# connectors.net
KiCad netlist of a schematic drawn in Altium Designer
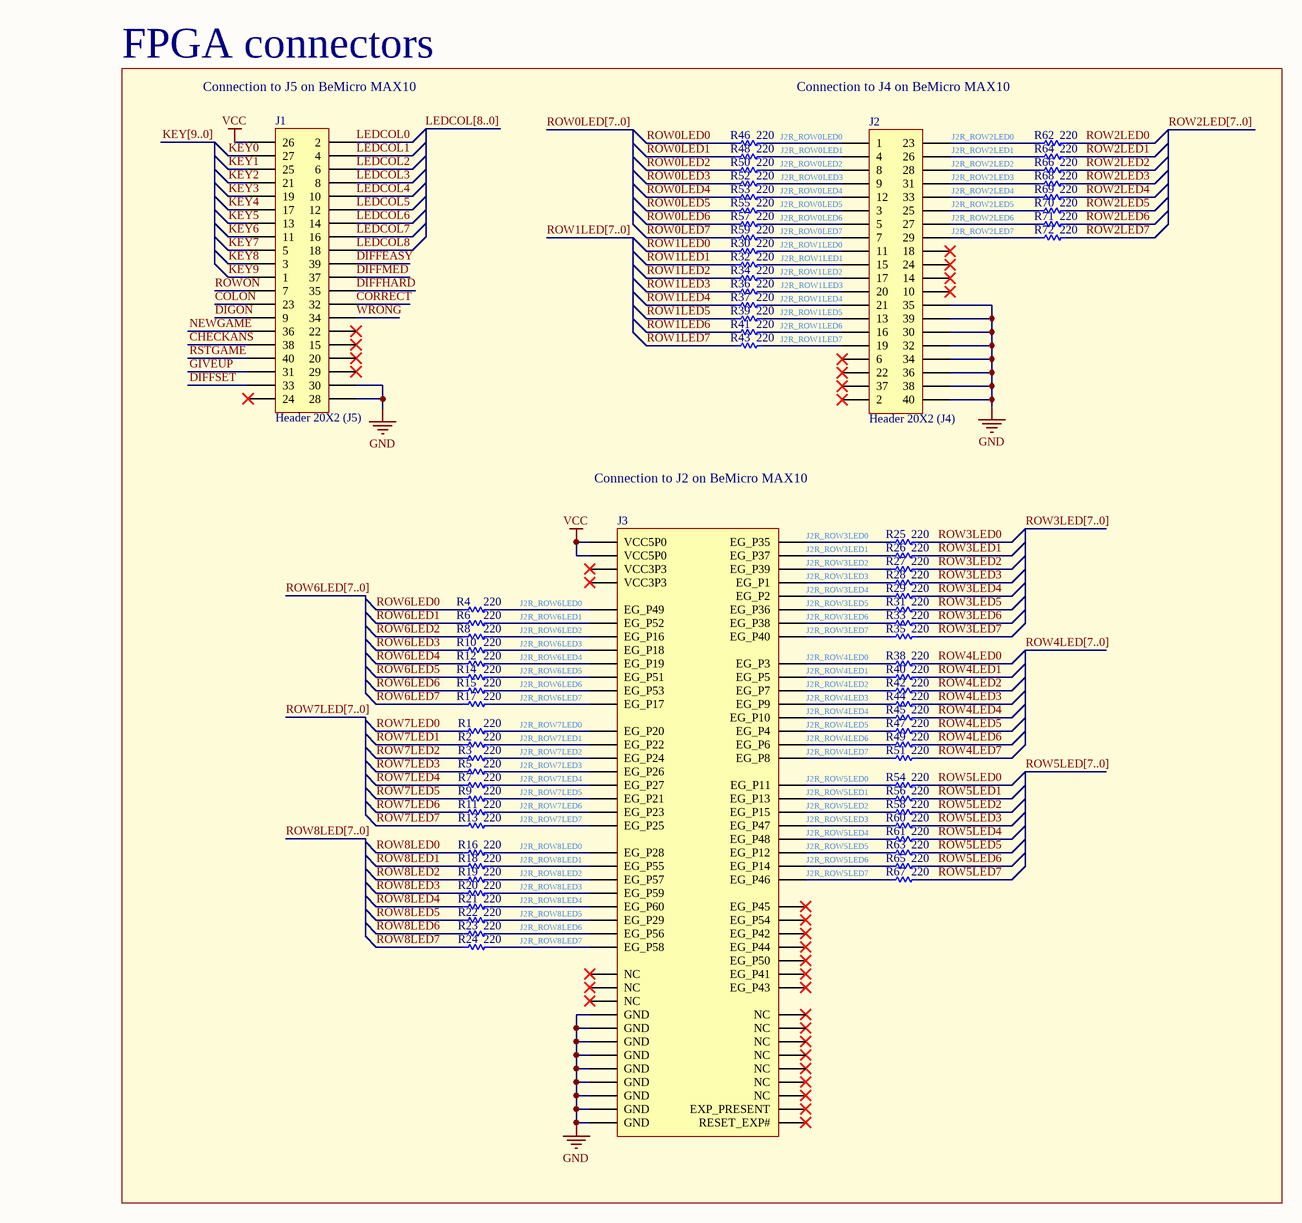
[diagram p0: connectors.SchDoc]

(export (version "E")
  (design (tool "Eeschema 10.0.6"))
  (components
    (comp (ref "J1")
      (value "Header 20X2 (J5)")
      (footprint "2x20")
      (description "Header, 20-Pin, Dual row")
      (fields (field (name "PUBLISHER") "Altium Limited"))
      (libsource (lib "") (part "Header 20X2_1"))
    )
    (comp (ref "J2")
      (value "Header 20X2 (J4)")
      (footprint "2x20")
      (description "Header, 20-Pin, Dual row")
      (fields (field (name "PUBLISHER") "Altium Limited"))
      (libsource (lib "bemicro_max10_fpga_connectors") (part "Header 20X2"))
    )
    (comp (ref "J3")
      (value "~")
      (footprint "SAMTEC_MEC6-140-02-L-D-RA1-TR")
      (description "Edge connector")
      (fields (field (name "MF") "Samtec") (field (name "MP") "MEC6-140-02-L-D-RA1-TR"))
      (libsource (lib "bemicro_max10_fpga_connectors") (part "MEC6-140-02-L-D-RA1-TR"))
    )
    (comp (ref "R1")
      (value "220")
      (footprint "SMD-0805-RES")
      (description "Resistor")
      (fields (field (name "Comment") "Res1") (field (name "PUBLISHER") "Altium Limited"))
      (libsource (lib "Miscellaneous Devices") (part "Res1"))
    )
    (comp (ref "R2")
      (value "220")
      (footprint "SMD-0805-RES")
      (description "Resistor")
      (fields (field (name "Comment") "Res1") (field (name "PUBLISHER") "Altium Limited"))
      (libsource (lib "Miscellaneous Devices") (part "Res1"))
    )
    (comp (ref "R3")
      (value "220")
      (footprint "SMD-0805-RES")
      (description "Resistor")
      (fields (field (name "Comment") "Res1") (field (name "PUBLISHER") "Altium Limited"))
      (libsource (lib "Miscellaneous Devices") (part "Res1"))
    )
    (comp (ref "R4")
      (value "220")
      (footprint "SMD-0805-RES")
      (description "Resistor")
      (fields (field (name "Comment") "Res1") (field (name "PUBLISHER") "Altium Limited"))
      (libsource (lib "Miscellaneous Devices") (part "Res1"))
    )
    (comp (ref "R5")
      (value "220")
      (footprint "SMD-0805-RES")
      (description "Resistor")
      (fields (field (name "Comment") "Res1") (field (name "PUBLISHER") "Altium Limited"))
      (libsource (lib "Miscellaneous Devices") (part "Res1"))
    )
    (comp (ref "R6")
      (value "220")
      (footprint "SMD-0805-RES")
      (description "Resistor")
      (fields (field (name "Comment") "Res1") (field (name "PUBLISHER") "Altium Limited"))
      (libsource (lib "Miscellaneous Devices") (part "Res1"))
    )
    (comp (ref "R7")
      (value "220")
      (footprint "SMD-0805-RES")
      (description "Resistor")
      (fields (field (name "Comment") "Res1") (field (name "PUBLISHER") "Altium Limited"))
      (libsource (lib "Miscellaneous Devices") (part "Res1"))
    )
    (comp (ref "R8")
      (value "220")
      (footprint "SMD-0805-RES")
      (description "Resistor")
      (fields (field (name "Comment") "Res1") (field (name "PUBLISHER") "Altium Limited"))
      (libsource (lib "Miscellaneous Devices") (part "Res1"))
    )
    (comp (ref "R9")
      (value "220")
      (footprint "SMD-0805-RES")
      (description "Resistor")
      (fields (field (name "Comment") "Res1") (field (name "PUBLISHER") "Altium Limited"))
      (libsource (lib "Miscellaneous Devices") (part "Res1"))
    )
    (comp (ref "R10")
      (value "220")
      (footprint "SMD-0805-RES")
      (description "Resistor")
      (fields (field (name "Comment") "Res1") (field (name "PUBLISHER") "Altium Limited"))
      (libsource (lib "Miscellaneous Devices") (part "Res1"))
    )
    (comp (ref "R11")
      (value "220")
      (footprint "SMD-0805-RES")
      (description "Resistor")
      (fields (field (name "Comment") "Res1") (field (name "PUBLISHER") "Altium Limited"))
      (libsource (lib "Miscellaneous Devices") (part "Res1"))
    )
    (comp (ref "R12")
      (value "220")
      (footprint "SMD-0805-RES")
      (description "Resistor")
      (fields (field (name "Comment") "Res1") (field (name "PUBLISHER") "Altium Limited"))
      (libsource (lib "Miscellaneous Devices") (part "Res1"))
    )
    (comp (ref "R13")
      (value "220")
      (footprint "SMD-0805-RES")
      (description "Resistor")
      (fields (field (name "Comment") "Res1") (field (name "PUBLISHER") "Altium Limited"))
      (libsource (lib "Miscellaneous Devices") (part "Res1"))
    )
    (comp (ref "R14")
      (value "220")
      (footprint "SMD-0805-RES")
      (description "Resistor")
      (fields (field (name "Comment") "Res1") (field (name "PUBLISHER") "Altium Limited"))
      (libsource (lib "Miscellaneous Devices") (part "Res1"))
    )
    (comp (ref "R15")
      (value "220")
      (footprint "SMD-0805-RES")
      (description "Resistor")
      (fields (field (name "Comment") "Res1") (field (name "PUBLISHER") "Altium Limited"))
      (libsource (lib "Miscellaneous Devices") (part "Res1"))
    )
    (comp (ref "R16")
      (value "220")
      (footprint "SMD-0805-RES")
      (description "Resistor")
      (fields (field (name "Comment") "Res1") (field (name "PUBLISHER") "Altium Limited"))
      (libsource (lib "Miscellaneous Devices") (part "Res1"))
    )
    (comp (ref "R17")
      (value "220")
      (footprint "SMD-0805-RES")
      (description "Resistor")
      (fields (field (name "Comment") "Res1") (field (name "PUBLISHER") "Altium Limited"))
      (libsource (lib "Miscellaneous Devices") (part "Res1"))
    )
    (comp (ref "R18")
      (value "220")
      (footprint "SMD-0805-RES")
      (description "Resistor")
      (fields (field (name "Comment") "Res1") (field (name "PUBLISHER") "Altium Limited"))
      (libsource (lib "Miscellaneous Devices") (part "Res1"))
    )
    (comp (ref "R19")
      (value "220")
      (footprint "SMD-0805-RES")
      (description "Resistor")
      (fields (field (name "Comment") "Res1") (field (name "PUBLISHER") "Altium Limited"))
      (libsource (lib "Miscellaneous Devices") (part "Res1"))
    )
    (comp (ref "R20")
      (value "220")
      (footprint "SMD-0805-RES")
      (description "Resistor")
      (fields (field (name "Comment") "Res1") (field (name "PUBLISHER") "Altium Limited"))
      (libsource (lib "Miscellaneous Devices") (part "Res1"))
    )
    (comp (ref "R21")
      (value "220")
      (footprint "SMD-0805-RES")
      (description "Resistor")
      (fields (field (name "Comment") "Res1") (field (name "PUBLISHER") "Altium Limited"))
      (libsource (lib "Miscellaneous Devices") (part "Res1"))
    )
    (comp (ref "R22")
      (value "220")
      (footprint "SMD-0805-RES")
      (description "Resistor")
      (fields (field (name "Comment") "Res1") (field (name "PUBLISHER") "Altium Limited"))
      (libsource (lib "Miscellaneous Devices") (part "Res1"))
    )
    (comp (ref "R23")
      (value "220")
      (footprint "SMD-0805-RES")
      (description "Resistor")
      (fields (field (name "Comment") "Res1") (field (name "PUBLISHER") "Altium Limited"))
      (libsource (lib "Miscellaneous Devices") (part "Res1"))
    )
    (comp (ref "R24")
      (value "220")
      (footprint "SMD-0805-RES")
      (description "Resistor")
      (fields (field (name "Comment") "Res1") (field (name "PUBLISHER") "Altium Limited"))
      (libsource (lib "Miscellaneous Devices") (part "Res1"))
    )
    (comp (ref "R25")
      (value "220")
      (footprint "SMD-0805-RES")
      (description "Resistor")
      (fields (field (name "Comment") "Res1") (field (name "PUBLISHER") "Altium Limited"))
      (libsource (lib "Miscellaneous Devices") (part "Res1"))
    )
    (comp (ref "R26")
      (value "220")
      (footprint "SMD-0805-RES")
      (description "Resistor")
      (fields (field (name "Comment") "Res1") (field (name "PUBLISHER") "Altium Limited"))
      (libsource (lib "Miscellaneous Devices") (part "Res1"))
    )
    (comp (ref "R27")
      (value "220")
      (footprint "SMD-0805-RES")
      (description "Resistor")
      (fields (field (name "Comment") "Res1") (field (name "PUBLISHER") "Altium Limited"))
      (libsource (lib "Miscellaneous Devices") (part "Res1"))
    )
    (comp (ref "R28")
      (value "220")
      (footprint "SMD-0805-RES")
      (description "Resistor")
      (fields (field (name "Comment") "Res1") (field (name "PUBLISHER") "Altium Limited"))
      (libsource (lib "Miscellaneous Devices") (part "Res1"))
    )
    (comp (ref "R29")
      (value "220")
      (footprint "SMD-0805-RES")
      (description "Resistor")
      (fields (field (name "Comment") "Res1") (field (name "PUBLISHER") "Altium Limited"))
      (libsource (lib "Miscellaneous Devices") (part "Res1"))
    )
    (comp (ref "R30")
      (value "220")
      (footprint "SMD-0805-RES")
      (description "Resistor")
      (fields (field (name "Comment") "Res1") (field (name "PUBLISHER") "Altium Limited"))
      (libsource (lib "Miscellaneous Devices") (part "Res1"))
    )
    (comp (ref "R31")
      (value "220")
      (footprint "SMD-0805-RES")
      (description "Resistor")
      (fields (field (name "Comment") "Res1") (field (name "PUBLISHER") "Altium Limited"))
      (libsource (lib "Miscellaneous Devices") (part "Res1"))
    )
    (comp (ref "R32")
      (value "220")
      (footprint "SMD-0805-RES")
      (description "Resistor")
      (fields (field (name "Comment") "Res1") (field (name "PUBLISHER") "Altium Limited"))
      (libsource (lib "Miscellaneous Devices") (part "Res1"))
    )
    (comp (ref "R33")
      (value "220")
      (footprint "SMD-0805-RES")
      (description "Resistor")
      (fields (field (name "Comment") "Res1") (field (name "PUBLISHER") "Altium Limited"))
      (libsource (lib "Miscellaneous Devices") (part "Res1"))
    )
    (comp (ref "R34")
      (value "220")
      (footprint "SMD-0805-RES")
      (description "Resistor")
      (fields (field (name "Comment") "Res1") (field (name "PUBLISHER") "Altium Limited"))
      (libsource (lib "Miscellaneous Devices") (part "Res1"))
    )
    (comp (ref "R35")
      (value "220")
      (footprint "SMD-0805-RES")
      (description "Resistor")
      (fields (field (name "Comment") "Res1") (field (name "PUBLISHER") "Altium Limited"))
      (libsource (lib "Miscellaneous Devices") (part "Res1"))
    )
    (comp (ref "R36")
      (value "220")
      (footprint "SMD-0805-RES")
      (description "Resistor")
      (fields (field (name "Comment") "Res1") (field (name "PUBLISHER") "Altium Limited"))
      (libsource (lib "Miscellaneous Devices") (part "Res1"))
    )
    (comp (ref "R37")
      (value "220")
      (footprint "SMD-0805-RES")
      (description "Resistor")
      (fields (field (name "Comment") "Res1") (field (name "PUBLISHER") "Altium Limited"))
      (libsource (lib "Miscellaneous Devices") (part "Res1"))
    )
    (comp (ref "R38")
      (value "220")
      (footprint "SMD-0805-RES")
      (description "Resistor")
      (fields (field (name "Comment") "Res1") (field (name "PUBLISHER") "Altium Limited"))
      (libsource (lib "Miscellaneous Devices") (part "Res1"))
    )
    (comp (ref "R39")
      (value "220")
      (footprint "SMD-0805-RES")
      (description "Resistor")
      (fields (field (name "Comment") "Res1") (field (name "PUBLISHER") "Altium Limited"))
      (libsource (lib "Miscellaneous Devices") (part "Res1"))
    )
    (comp (ref "R40")
      (value "220")
      (footprint "SMD-0805-RES")
      (description "Resistor")
      (fields (field (name "Comment") "Res1") (field (name "PUBLISHER") "Altium Limited"))
      (libsource (lib "Miscellaneous Devices") (part "Res1"))
    )
    (comp (ref "R41")
      (value "220")
      (footprint "SMD-0805-RES")
      (description "Resistor")
      (fields (field (name "Comment") "Res1") (field (name "PUBLISHER") "Altium Limited"))
      (libsource (lib "Miscellaneous Devices") (part "Res1"))
    )
    (comp (ref "R42")
      (value "220")
      (footprint "SMD-0805-RES")
      (description "Resistor")
      (fields (field (name "Comment") "Res1") (field (name "PUBLISHER") "Altium Limited"))
      (libsource (lib "Miscellaneous Devices") (part "Res1"))
    )
    (comp (ref "R43")
      (value "220")
      (footprint "SMD-0805-RES")
      (description "Resistor")
      (fields (field (name "Comment") "Res1") (field (name "PUBLISHER") "Altium Limited"))
      (libsource (lib "Miscellaneous Devices") (part "Res1"))
    )
    (comp (ref "R44")
      (value "220")
      (footprint "SMD-0805-RES")
      (description "Resistor")
      (fields (field (name "Comment") "Res1") (field (name "PUBLISHER") "Altium Limited"))
      (libsource (lib "Miscellaneous Devices") (part "Res1"))
    )
    (comp (ref "R45")
      (value "220")
      (footprint "SMD-0805-RES")
      (description "Resistor")
      (fields (field (name "Comment") "Res1") (field (name "PUBLISHER") "Altium Limited"))
      (libsource (lib "Miscellaneous Devices") (part "Res1"))
    )
    (comp (ref "R46")
      (value "220")
      (footprint "SMD-0805-RES")
      (description "Resistor")
      (fields (field (name "Comment") "Res1") (field (name "PUBLISHER") "Altium Limited"))
      (libsource (lib "Miscellaneous Devices") (part "Res1"))
    )
    (comp (ref "R47")
      (value "220")
      (footprint "SMD-0805-RES")
      (description "Resistor")
      (fields (field (name "Comment") "Res1") (field (name "PUBLISHER") "Altium Limited"))
      (libsource (lib "Miscellaneous Devices") (part "Res1"))
    )
    (comp (ref "R48")
      (value "220")
      (footprint "SMD-0805-RES")
      (description "Resistor")
      (fields (field (name "Comment") "Res1") (field (name "PUBLISHER") "Altium Limited"))
      (libsource (lib "Miscellaneous Devices") (part "Res1"))
    )
    (comp (ref "R49")
      (value "220")
      (footprint "SMD-0805-RES")
      (description "Resistor")
      (fields (field (name "Comment") "Res1") (field (name "PUBLISHER") "Altium Limited"))
      (libsource (lib "Miscellaneous Devices") (part "Res1"))
    )
    (comp (ref "R50")
      (value "220")
      (footprint "SMD-0805-RES")
      (description "Resistor")
      (fields (field (name "Comment") "Res1") (field (name "PUBLISHER") "Altium Limited"))
      (libsource (lib "Miscellaneous Devices") (part "Res1"))
    )
    (comp (ref "R51")
      (value "220")
      (footprint "SMD-0805-RES")
      (description "Resistor")
      (fields (field (name "Comment") "Res1") (field (name "PUBLISHER") "Altium Limited"))
      (libsource (lib "Miscellaneous Devices") (part "Res1"))
    )
    (comp (ref "R52")
      (value "220")
      (footprint "SMD-0805-RES")
      (description "Resistor")
      (fields (field (name "Comment") "Res1") (field (name "PUBLISHER") "Altium Limited"))
      (libsource (lib "Miscellaneous Devices") (part "Res1"))
    )
    (comp (ref "R53")
      (value "220")
      (footprint "SMD-0805-RES")
      (description "Resistor")
      (fields (field (name "Comment") "Res1") (field (name "PUBLISHER") "Altium Limited"))
      (libsource (lib "Miscellaneous Devices") (part "Res1"))
    )
    (comp (ref "R54")
      (value "220")
      (footprint "SMD-0805-RES")
      (description "Resistor")
      (fields (field (name "Comment") "Res1") (field (name "PUBLISHER") "Altium Limited"))
      (libsource (lib "Miscellaneous Devices") (part "Res1"))
    )
    (comp (ref "R55")
      (value "220")
      (footprint "SMD-0805-RES")
      (description "Resistor")
      (fields (field (name "Comment") "Res1") (field (name "PUBLISHER") "Altium Limited"))
      (libsource (lib "Miscellaneous Devices") (part "Res1"))
    )
    (comp (ref "R56")
      (value "220")
      (footprint "SMD-0805-RES")
      (description "Resistor")
      (fields (field (name "Comment") "Res1") (field (name "PUBLISHER") "Altium Limited"))
      (libsource (lib "Miscellaneous Devices") (part "Res1"))
    )
    (comp (ref "R57")
      (value "220")
      (footprint "SMD-0805-RES")
      (description "Resistor")
      (fields (field (name "Comment") "Res1") (field (name "PUBLISHER") "Altium Limited"))
      (libsource (lib "Miscellaneous Devices") (part "Res1"))
    )
    (comp (ref "R58")
      (value "220")
      (footprint "SMD-0805-RES")
      (description "Resistor")
      (fields (field (name "Comment") "Res1") (field (name "PUBLISHER") "Altium Limited"))
      (libsource (lib "Miscellaneous Devices") (part "Res1"))
    )
    (comp (ref "R59")
      (value "220")
      (footprint "SMD-0805-RES")
      (description "Resistor")
      (fields (field (name "Comment") "Res1") (field (name "PUBLISHER") "Altium Limited"))
      (libsource (lib "Miscellaneous Devices") (part "Res1"))
    )
    (comp (ref "R60")
      (value "220")
      (footprint "SMD-0805-RES")
      (description "Resistor")
      (fields (field (name "Comment") "Res1") (field (name "PUBLISHER") "Altium Limited"))
      (libsource (lib "Miscellaneous Devices") (part "Res1"))
    )
    (comp (ref "R61")
      (value "220")
      (footprint "SMD-0805-RES")
      (description "Resistor")
      (fields (field (name "Comment") "Res1") (field (name "PUBLISHER") "Altium Limited"))
      (libsource (lib "Miscellaneous Devices") (part "Res1"))
    )
    (comp (ref "R62")
      (value "220")
      (footprint "SMD-0805-RES")
      (description "Resistor")
      (fields (field (name "Comment") "Res1") (field (name "PUBLISHER") "Altium Limited"))
      (libsource (lib "Miscellaneous Devices") (part "Res1"))
    )
    (comp (ref "R63")
      (value "220")
      (footprint "SMD-0805-RES")
      (description "Resistor")
      (fields (field (name "Comment") "Res1") (field (name "PUBLISHER") "Altium Limited"))
      (libsource (lib "Miscellaneous Devices") (part "Res1"))
    )
    (comp (ref "R64")
      (value "220")
      (footprint "SMD-0805-RES")
      (description "Resistor")
      (fields (field (name "Comment") "Res1") (field (name "PUBLISHER") "Altium Limited"))
      (libsource (lib "Miscellaneous Devices") (part "Res1"))
    )
    (comp (ref "R65")
      (value "220")
      (footprint "SMD-0805-RES")
      (description "Resistor")
      (fields (field (name "Comment") "Res1") (field (name "PUBLISHER") "Altium Limited"))
      (libsource (lib "Miscellaneous Devices") (part "Res1"))
    )
    (comp (ref "R66")
      (value "220")
      (footprint "SMD-0805-RES")
      (description "Resistor")
      (fields (field (name "Comment") "Res1") (field (name "PUBLISHER") "Altium Limited"))
      (libsource (lib "Miscellaneous Devices") (part "Res1"))
    )
    (comp (ref "R67")
      (value "220")
      (footprint "SMD-0805-RES")
      (description "Resistor")
      (fields (field (name "Comment") "Res1") (field (name "PUBLISHER") "Altium Limited"))
      (libsource (lib "Miscellaneous Devices") (part "Res1"))
    )
    (comp (ref "R68")
      (value "220")
      (footprint "SMD-0805-RES")
      (description "Resistor")
      (fields (field (name "Comment") "Res1") (field (name "PUBLISHER") "Altium Limited"))
      (libsource (lib "Miscellaneous Devices") (part "Res1"))
    )
    (comp (ref "R69")
      (value "220")
      (footprint "SMD-0805-RES")
      (description "Resistor")
      (fields (field (name "Comment") "Res1") (field (name "PUBLISHER") "Altium Limited"))
      (libsource (lib "Miscellaneous Devices") (part "Res1"))
    )
    (comp (ref "R70")
      (value "220")
      (footprint "SMD-0805-RES")
      (description "Resistor")
      (fields (field (name "Comment") "Res1") (field (name "PUBLISHER") "Altium Limited"))
      (libsource (lib "Miscellaneous Devices") (part "Res1"))
    )
    (comp (ref "R71")
      (value "220")
      (footprint "SMD-0805-RES")
      (description "Resistor")
      (fields (field (name "Comment") "Res1") (field (name "PUBLISHER") "Altium Limited"))
      (libsource (lib "Miscellaneous Devices") (part "Res1"))
    )
    (comp (ref "R72")
      (value "220")
      (footprint "SMD-0805-RES")
      (description "Resistor")
      (fields (field (name "Comment") "Res1") (field (name "PUBLISHER") "Altium Limited"))
      (libsource (lib "Miscellaneous Devices") (part "Res1"))
    )
  )
  (nets
    (net (code "1") (name "/CHECKANS") (class "Default")
      (node (ref "J1") (pin "38") (pinfunction "38_38") (pintype "passive"))
    )
    (net (code "2") (name "/COLON") (class "Default")
      (node (ref "J1") (pin "23") (pinfunction "23_23") (pintype "passive"))
    )
    (net (code "3") (name "/CORRECT") (class "Default")
      (node (ref "J1") (pin "32") (pinfunction "32_32") (pintype "passive"))
    )
    (net (code "4") (name "/DIFFEASY") (class "Default")
      (node (ref "J1") (pin "39") (pinfunction "39_39") (pintype "passive"))
    )
    (net (code "5") (name "/DIFFHARD") (class "Default")
      (node (ref "J1") (pin "35") (pinfunction "35_35") (pintype "passive"))
    )
    (net (code "6") (name "/DIFFMED") (class "Default")
      (node (ref "J1") (pin "37") (pinfunction "37_37") (pintype "passive"))
    )
    (net (code "7") (name "/DIFFSET") (class "Default")
      (node (ref "J1") (pin "33") (pinfunction "33_33") (pintype "passive"))
    )
    (net (code "8") (name "/DIGON") (class "Default")
      (node (ref "J1") (pin "9") (pinfunction "9_9") (pintype "passive"))
    )
    (net (code "9") (name "/GIVEUP") (class "Default")
      (node (ref "J1") (pin "31") (pinfunction "31_31") (pintype "passive"))
    )
    (net (code "10") (name "/J2R_ROW0LED0") (class "Default")
      (node (ref "J2") (pin "1") (pinfunction "1_1") (pintype "passive"))
      (node (ref "R46") (pin "2") (pinfunction "2_2") (pintype "passive"))
    )
    (net (code "11") (name "/J2R_ROW0LED1") (class "Default")
      (node (ref "J2") (pin "4") (pinfunction "4_4") (pintype "passive"))
      (node (ref "R48") (pin "2") (pinfunction "2_2") (pintype "passive"))
    )
    (net (code "12") (name "/J2R_ROW0LED2") (class "Default")
      (node (ref "J2") (pin "8") (pinfunction "8_8") (pintype "passive"))
      (node (ref "R50") (pin "2") (pinfunction "2_2") (pintype "passive"))
    )
    (net (code "13") (name "/J2R_ROW0LED3") (class "Default")
      (node (ref "J2") (pin "9") (pinfunction "9_9") (pintype "passive"))
      (node (ref "R52") (pin "2") (pinfunction "2_2") (pintype "passive"))
    )
    (net (code "14") (name "/J2R_ROW0LED4") (class "Default")
      (node (ref "J2") (pin "12") (pinfunction "12_12") (pintype "passive"))
      (node (ref "R53") (pin "2") (pinfunction "2_2") (pintype "passive"))
    )
    (net (code "15") (name "/J2R_ROW0LED5") (class "Default")
      (node (ref "J2") (pin "3") (pinfunction "3_3") (pintype "passive"))
      (node (ref "R55") (pin "2") (pinfunction "2_2") (pintype "passive"))
    )
    (net (code "16") (name "/J2R_ROW0LED6") (class "Default")
      (node (ref "J2") (pin "5") (pinfunction "5_5") (pintype "passive"))
      (node (ref "R57") (pin "2") (pinfunction "2_2") (pintype "passive"))
    )
    (net (code "17") (name "/J2R_ROW0LED7") (class "Default")
      (node (ref "J2") (pin "7") (pinfunction "7_7") (pintype "passive"))
      (node (ref "R59") (pin "2") (pinfunction "2_2") (pintype "passive"))
    )
    (net (code "18") (name "/J2R_ROW1LED0") (class "Default")
      (node (ref "J2") (pin "11") (pinfunction "11_11") (pintype "passive"))
      (node (ref "R30") (pin "2") (pinfunction "2_2") (pintype "passive"))
    )
    (net (code "19") (name "/J2R_ROW1LED1") (class "Default")
      (node (ref "J2") (pin "15") (pinfunction "15_15") (pintype "passive"))
      (node (ref "R32") (pin "2") (pinfunction "2_2") (pintype "passive"))
    )
    (net (code "20") (name "/J2R_ROW1LED2") (class "Default")
      (node (ref "J2") (pin "17") (pinfunction "17_17") (pintype "passive"))
      (node (ref "R34") (pin "2") (pinfunction "2_2") (pintype "passive"))
    )
    (net (code "21") (name "/J2R_ROW1LED3") (class "Default")
      (node (ref "J2") (pin "20") (pinfunction "20_20") (pintype "passive"))
      (node (ref "R36") (pin "2") (pinfunction "2_2") (pintype "passive"))
    )
    (net (code "22") (name "/J2R_ROW1LED4") (class "Default")
      (node (ref "J2") (pin "21") (pinfunction "21_21") (pintype "passive"))
      (node (ref "R37") (pin "2") (pinfunction "2_2") (pintype "passive"))
    )
    (net (code "23") (name "/J2R_ROW1LED5") (class "Default")
      (node (ref "J2") (pin "13") (pinfunction "13_13") (pintype "passive"))
      (node (ref "R39") (pin "2") (pinfunction "2_2") (pintype "passive"))
    )
    (net (code "24") (name "/J2R_ROW1LED6") (class "Default")
      (node (ref "J2") (pin "16") (pinfunction "16_16") (pintype "passive"))
      (node (ref "R41") (pin "2") (pinfunction "2_2") (pintype "passive"))
    )
    (net (code "25") (name "/J2R_ROW1LED7") (class "Default")
      (node (ref "J2") (pin "19") (pinfunction "19_19") (pintype "passive"))
      (node (ref "R43") (pin "2") (pinfunction "2_2") (pintype "passive"))
    )
    (net (code "26") (name "/J2R_ROW2LED0") (class "Default")
      (node (ref "J2") (pin "23") (pinfunction "23_23") (pintype "passive"))
      (node (ref "R62") (pin "1") (pinfunction "1_1") (pintype "passive"))
    )
    (net (code "27") (name "/J2R_ROW2LED1") (class "Default")
      (node (ref "J2") (pin "26") (pinfunction "26_26") (pintype "passive"))
      (node (ref "R64") (pin "1") (pinfunction "1_1") (pintype "passive"))
    )
    (net (code "28") (name "/J2R_ROW2LED2") (class "Default")
      (node (ref "J2") (pin "28") (pinfunction "28_28") (pintype "passive"))
      (node (ref "R66") (pin "1") (pinfunction "1_1") (pintype "passive"))
    )
    (net (code "29") (name "/J2R_ROW2LED3") (class "Default")
      (node (ref "J2") (pin "31") (pinfunction "31_31") (pintype "passive"))
      (node (ref "R68") (pin "1") (pinfunction "1_1") (pintype "passive"))
    )
    (net (code "30") (name "/J2R_ROW2LED4") (class "Default")
      (node (ref "J2") (pin "33") (pinfunction "33_33") (pintype "passive"))
      (node (ref "R69") (pin "1") (pinfunction "1_1") (pintype "passive"))
    )
    (net (code "31") (name "/J2R_ROW2LED5") (class "Default")
      (node (ref "J2") (pin "25") (pinfunction "25_25") (pintype "passive"))
      (node (ref "R70") (pin "1") (pinfunction "1_1") (pintype "passive"))
    )
    (net (code "32") (name "/J2R_ROW2LED6") (class "Default")
      (node (ref "J2") (pin "27") (pinfunction "27_27") (pintype "passive"))
      (node (ref "R71") (pin "1") (pinfunction "1_1") (pintype "passive"))
    )
    (net (code "33") (name "/J2R_ROW2LED7") (class "Default")
      (node (ref "J2") (pin "29") (pinfunction "29_29") (pintype "passive"))
      (node (ref "R72") (pin "1") (pinfunction "1_1") (pintype "passive"))
    )
    (net (code "34") (name "/J2R_ROW3LED0") (class "Default")
      (node (ref "J3") (pin "06") (pinfunction "EG_P35_06") (pintype "passive"))
      (node (ref "R25") (pin "1") (pinfunction "1_1") (pintype "passive"))
    )
    (net (code "35") (name "/J2R_ROW3LED1") (class "Default")
      (node (ref "J3") (pin "12") (pinfunction "EG_P37_12") (pintype "passive"))
      (node (ref "R26") (pin "1") (pinfunction "1_1") (pintype "passive"))
    )
    (net (code "36") (name "/J2R_ROW3LED2") (class "Default")
      (node (ref "J3") (pin "16") (pinfunction "EG_P39_16") (pintype "passive"))
      (node (ref "R27") (pin "1") (pinfunction "1_1") (pintype "passive"))
    )
    (net (code "37") (name "/J2R_ROW3LED3") (class "Default")
      (node (ref "J3") (pin "05") (pinfunction "EG_P1_05") (pintype "passive"))
      (node (ref "R28") (pin "1") (pinfunction "1_1") (pintype "passive"))
    )
    (net (code "38") (name "/J2R_ROW3LED4") (class "Default")
      (node (ref "J3") (pin "07") (pinfunction "EG_P2_07") (pintype "passive"))
      (node (ref "R29") (pin "1") (pinfunction "1_1") (pintype "passive"))
    )
    (net (code "39") (name "/J2R_ROW3LED5") (class "Default")
      (node (ref "J3") (pin "08") (pinfunction "EG_P36_08") (pintype "passive"))
      (node (ref "R31") (pin "1") (pinfunction "1_1") (pintype "passive"))
    )
    (net (code "40") (name "/J2R_ROW3LED6") (class "Default")
      (node (ref "J3") (pin "14") (pinfunction "EG_P38_14") (pintype "passive"))
      (node (ref "R33") (pin "1") (pinfunction "1_1") (pintype "passive"))
    )
    (net (code "41") (name "/J2R_ROW3LED7") (class "Default")
      (node (ref "J3") (pin "18") (pinfunction "EG_P40_18") (pintype "passive"))
      (node (ref "R35") (pin "1") (pinfunction "1_1") (pintype "passive"))
    )
    (net (code "42") (name "/J2R_ROW4LED0") (class "Default")
      (node (ref "J3") (pin "09") (pinfunction "EG_P3_09") (pintype "passive"))
      (node (ref "R38") (pin "1") (pinfunction "1_1") (pintype "passive"))
    )
    (net (code "43") (name "/J2R_ROW4LED1") (class "Default")
      (node (ref "J3") (pin "13") (pinfunction "EG_P5_13") (pintype "passive"))
      (node (ref "R40") (pin "1") (pinfunction "1_1") (pintype "passive"))
    )
    (net (code "44") (name "/J2R_ROW4LED2") (class "Default")
      (node (ref "J3") (pin "17") (pinfunction "EG_P7_17") (pintype "passive"))
      (node (ref "R42") (pin "1") (pinfunction "1_1") (pintype "passive"))
    )
    (net (code "45") (name "/J2R_ROW4LED3") (class "Default")
      (node (ref "J3") (pin "23") (pinfunction "EG_P9_23") (pintype "passive"))
      (node (ref "R44") (pin "1") (pinfunction "1_1") (pintype "passive"))
    )
    (net (code "46") (name "/J2R_ROW4LED4") (class "Default")
      (node (ref "J3") (pin "25") (pinfunction "EG_P10_25") (pintype "passive"))
      (node (ref "R45") (pin "1") (pinfunction "1_1") (pintype "passive"))
    )
    (net (code "47") (name "/J2R_ROW4LED5") (class "Default")
      (node (ref "J3") (pin "11") (pinfunction "EG_P4_11") (pintype "passive"))
      (node (ref "R47") (pin "1") (pinfunction "1_1") (pintype "passive"))
    )
    (net (code "48") (name "/J2R_ROW4LED6") (class "Default")
      (node (ref "J3") (pin "15") (pinfunction "EG_P6_15") (pintype "passive"))
      (node (ref "R49") (pin "1") (pinfunction "1_1") (pintype "passive"))
    )
    (net (code "49") (name "/J2R_ROW4LED7") (class "Default")
      (node (ref "J3") (pin "19") (pinfunction "EG_P8_19") (pintype "passive"))
      (node (ref "R51") (pin "1") (pinfunction "1_1") (pintype "passive"))
    )
    (net (code "50") (name "/J2R_ROW5LED0") (class "Default")
      (node (ref "J3") (pin "27") (pinfunction "EG_P11_27") (pintype "passive"))
      (node (ref "R54") (pin "1") (pinfunction "1_1") (pintype "passive"))
    )
    (net (code "51") (name "/J2R_ROW5LED1") (class "Default")
      (node (ref "J3") (pin "31") (pinfunction "EG_P13_31") (pintype "passive"))
      (node (ref "R56") (pin "1") (pinfunction "1_1") (pintype "passive"))
    )
    (net (code "52") (name "/J2R_ROW5LED2") (class "Default")
      (node (ref "J3") (pin "37") (pinfunction "EG_P15_37") (pintype "passive"))
      (node (ref "R58") (pin "1") (pinfunction "1_1") (pintype "passive"))
    )
    (net (code "53") (name "/J2R_ROW5LED3") (class "Default")
      (node (ref "J3") (pin "36") (pinfunction "EG_P47_36") (pintype "passive"))
      (node (ref "R60") (pin "1") (pinfunction "1_1") (pintype "passive"))
    )
    (net (code "54") (name "/J2R_ROW5LED4") (class "Default")
      (node (ref "J3") (pin "38") (pinfunction "EG_P48_38") (pintype "passive"))
      (node (ref "R61") (pin "1") (pinfunction "1_1") (pintype "passive"))
    )
    (net (code "55") (name "/J2R_ROW5LED5") (class "Default")
      (node (ref "J3") (pin "29") (pinfunction "EG_P12_29") (pintype "passive"))
      (node (ref "R63") (pin "1") (pinfunction "1_1") (pintype "passive"))
    )
    (net (code "56") (name "/J2R_ROW5LED6") (class "Default")
      (node (ref "J3") (pin "35") (pinfunction "EG_P14_35") (pintype "passive"))
      (node (ref "R65") (pin "1") (pinfunction "1_1") (pintype "passive"))
    )
    (net (code "57") (name "/J2R_ROW5LED7") (class "Default")
      (node (ref "J3") (pin "34") (pinfunction "EG_P46_34") (pintype "passive"))
      (node (ref "R67") (pin "1") (pinfunction "1_1") (pintype "passive"))
    )
    (net (code "58") (name "/J2R_ROW6LED0") (class "Default")
      (node (ref "J3") (pin "40") (pinfunction "EG_P49_40") (pintype "passive"))
      (node (ref "R4") (pin "2") (pinfunction "2_2") (pintype "passive"))
    )
    (net (code "59") (name "/J2R_ROW6LED1") (class "Default")
      (node (ref "J3") (pin "48") (pinfunction "EG_P52_48") (pintype "passive"))
      (node (ref "R6") (pin "2") (pinfunction "2_2") (pintype "passive"))
    )
    (net (code "60") (name "/J2R_ROW6LED2") (class "Default")
      (node (ref "J3") (pin "39") (pinfunction "EG_P16_39") (pintype "passive"))
      (node (ref "R8") (pin "2") (pinfunction "2_2") (pintype "passive"))
    )
    (net (code "61") (name "/J2R_ROW6LED3") (class "Default")
      (node (ref "J3") (pin "43") (pinfunction "EG_P18_43") (pintype "passive"))
      (node (ref "R10") (pin "2") (pinfunction "2_2") (pintype "passive"))
    )
    (net (code "62") (name "/J2R_ROW6LED4") (class "Default")
      (node (ref "J3") (pin "45") (pinfunction "EG_P19_45") (pintype "passive"))
      (node (ref "R12") (pin "2") (pinfunction "2_2") (pintype "passive"))
    )
    (net (code "63") (name "/J2R_ROW6LED5") (class "Default")
      (node (ref "J3") (pin "46") (pinfunction "EG_P51_46") (pintype "passive"))
      (node (ref "R14") (pin "2") (pinfunction "2_2") (pintype "passive"))
    )
    (net (code "64") (name "/J2R_ROW6LED6") (class "Default")
      (node (ref "J3") (pin "50") (pinfunction "EG_P53_50") (pintype "passive"))
      (node (ref "R15") (pin "2") (pinfunction "2_2") (pintype "passive"))
    )
    (net (code "65") (name "/J2R_ROW6LED7") (class "Default")
      (node (ref "J3") (pin "41") (pinfunction "EG_P17_41") (pintype "passive"))
      (node (ref "R17") (pin "2") (pinfunction "2_2") (pintype "passive"))
    )
    (net (code "66") (name "/J2R_ROW7LED0") (class "Default")
      (node (ref "J3") (pin "47") (pinfunction "EG_P20_47") (pintype "passive"))
      (node (ref "R1") (pin "2") (pinfunction "2_2") (pintype "passive"))
    )
    (net (code "67") (name "/J2R_ROW7LED1") (class "Default")
      (node (ref "J3") (pin "51") (pinfunction "EG_P22_51") (pintype "passive"))
      (node (ref "R2") (pin "2") (pinfunction "2_2") (pintype "passive"))
    )
    (net (code "68") (name "/J2R_ROW7LED2") (class "Default")
      (node (ref "J3") (pin "57") (pinfunction "EG_P24_57") (pintype "passive"))
      (node (ref "R3") (pin "2") (pinfunction "2_2") (pintype "passive"))
    )
    (net (code "69") (name "/J2R_ROW7LED3") (class "Default")
      (node (ref "J3") (pin "61") (pinfunction "EG_P26_61") (pintype "passive"))
      (node (ref "R5") (pin "2") (pinfunction "2_2") (pintype "passive"))
    )
    (net (code "70") (name "/J2R_ROW7LED4") (class "Default")
      (node (ref "J3") (pin "63") (pinfunction "EG_P27_63") (pintype "passive"))
      (node (ref "R7") (pin "2") (pinfunction "2_2") (pintype "passive"))
    )
    (net (code "71") (name "/J2R_ROW7LED5") (class "Default")
      (node (ref "J3") (pin "49") (pinfunction "EG_P21_49") (pintype "passive"))
      (node (ref "R9") (pin "2") (pinfunction "2_2") (pintype "passive"))
    )
    (net (code "72") (name "/J2R_ROW7LED6") (class "Default")
      (node (ref "J3") (pin "55") (pinfunction "EG_P23_55") (pintype "passive"))
      (node (ref "R11") (pin "2") (pinfunction "2_2") (pintype "passive"))
    )
    (net (code "73") (name "/J2R_ROW7LED7") (class "Default")
      (node (ref "J3") (pin "59") (pinfunction "EG_P25_59") (pintype "passive"))
      (node (ref "R13") (pin "2") (pinfunction "2_2") (pintype "passive"))
    )
    (net (code "74") (name "/J2R_ROW8LED0") (class "Default")
      (node (ref "J3") (pin "65") (pinfunction "EG_P28_65") (pintype "passive"))
      (node (ref "R16") (pin "2") (pinfunction "2_2") (pintype "passive"))
    )
    (net (code "75") (name "/J2R_ROW8LED1") (class "Default")
      (node (ref "J3") (pin "56") (pinfunction "EG_P55_56") (pintype "passive"))
      (node (ref "R18") (pin "2") (pinfunction "2_2") (pintype "passive"))
    )
    (net (code "76") (name "/J2R_ROW8LED2") (class "Default")
      (node (ref "J3") (pin "60") (pinfunction "EG_P57_60") (pintype "passive"))
      (node (ref "R19") (pin "2") (pinfunction "2_2") (pintype "passive"))
    )
    (net (code "77") (name "/J2R_ROW8LED3") (class "Default")
      (node (ref "J3") (pin "64") (pinfunction "EG_P59_64") (pintype "passive"))
      (node (ref "R20") (pin "2") (pinfunction "2_2") (pintype "passive"))
    )
    (net (code "78") (name "/J2R_ROW8LED4") (class "Default")
      (node (ref "J3") (pin "66") (pinfunction "EG_P60_66") (pintype "passive"))
      (node (ref "R21") (pin "2") (pinfunction "2_2") (pintype "passive"))
    )
    (net (code "79") (name "/J2R_ROW8LED5") (class "Default")
      (node (ref "J3") (pin "67") (pinfunction "EG_P29_67") (pintype "passive"))
      (node (ref "R22") (pin "2") (pinfunction "2_2") (pintype "passive"))
    )
    (net (code "80") (name "/J2R_ROW8LED6") (class "Default")
      (node (ref "J3") (pin "58") (pinfunction "EG_P56_58") (pintype "passive"))
      (node (ref "R23") (pin "2") (pinfunction "2_2") (pintype "passive"))
    )
    (net (code "81") (name "/J2R_ROW8LED7") (class "Default")
      (node (ref "J3") (pin "62") (pinfunction "EG_P58_62") (pintype "passive"))
      (node (ref "R24") (pin "2") (pinfunction "2_2") (pintype "passive"))
    )
    (net (code "82") (name "/KEY0") (class "Default")
      (node (ref "J1") (pin "27") (pinfunction "27_27") (pintype "passive"))
    )
    (net (code "83") (name "/KEY1") (class "Default")
      (node (ref "J1") (pin "25") (pinfunction "25_25") (pintype "passive"))
    )
    (net (code "84") (name "/KEY2") (class "Default")
      (node (ref "J1") (pin "21") (pinfunction "21_21") (pintype "passive"))
    )
    (net (code "85") (name "/KEY3") (class "Default")
      (node (ref "J1") (pin "19") (pinfunction "19_19") (pintype "passive"))
    )
    (net (code "86") (name "/KEY4") (class "Default")
      (node (ref "J1") (pin "17") (pinfunction "17_17") (pintype "passive"))
    )
    (net (code "87") (name "/KEY5") (class "Default")
      (node (ref "J1") (pin "13") (pinfunction "13_13") (pintype "passive"))
    )
    (net (code "88") (name "/KEY6") (class "Default")
      (node (ref "J1") (pin "11") (pinfunction "11_11") (pintype "passive"))
    )
    (net (code "89") (name "/KEY7") (class "Default")
      (node (ref "J1") (pin "5") (pinfunction "5_5") (pintype "passive"))
    )
    (net (code "90") (name "/KEY8") (class "Default")
      (node (ref "J1") (pin "3") (pinfunction "3_3") (pintype "passive"))
    )
    (net (code "91") (name "/KEY9") (class "Default")
      (node (ref "J1") (pin "1") (pinfunction "1_1") (pintype "passive"))
    )
    (net (code "93") (name "/LEDCOL0") (class "Default")
      (node (ref "J1") (pin "2") (pinfunction "2_2") (pintype "passive"))
    )
    (net (code "94") (name "/LEDCOL1") (class "Default")
      (node (ref "J1") (pin "4") (pinfunction "4_4") (pintype "passive"))
    )
    (net (code "95") (name "/LEDCOL2") (class "Default")
      (node (ref "J1") (pin "6") (pinfunction "6_6") (pintype "passive"))
    )
    (net (code "96") (name "/LEDCOL3") (class "Default")
      (node (ref "J1") (pin "8") (pinfunction "8_8") (pintype "passive"))
    )
    (net (code "97") (name "/LEDCOL4") (class "Default")
      (node (ref "J1") (pin "10") (pinfunction "10_10") (pintype "passive"))
    )
    (net (code "98") (name "/LEDCOL5") (class "Default")
      (node (ref "J1") (pin "12") (pinfunction "12_12") (pintype "passive"))
    )
    (net (code "99") (name "/LEDCOL6") (class "Default")
      (node (ref "J1") (pin "14") (pinfunction "14_14") (pintype "passive"))
    )
    (net (code "100") (name "/LEDCOL7") (class "Default")
      (node (ref "J1") (pin "16") (pinfunction "16_16") (pintype "passive"))
    )
    (net (code "101") (name "/LEDCOL8") (class "Default")
      (node (ref "J1") (pin "18") (pinfunction "18_18") (pintype "passive"))
    )
    (net (code "103") (name "/NEWGAME") (class "Default")
      (node (ref "J1") (pin "36") (pinfunction "36_36") (pintype "passive"))
    )
    (net (code "104") (name "/ROW0LED0") (class "Default")
      (node (ref "R46") (pin "1") (pinfunction "1_1") (pintype "passive"))
    )
    (net (code "105") (name "/ROW0LED1") (class "Default")
      (node (ref "R48") (pin "1") (pinfunction "1_1") (pintype "passive"))
    )
    (net (code "106") (name "/ROW0LED2") (class "Default")
      (node (ref "R50") (pin "1") (pinfunction "1_1") (pintype "passive"))
    )
    (net (code "107") (name "/ROW0LED3") (class "Default")
      (node (ref "R52") (pin "1") (pinfunction "1_1") (pintype "passive"))
    )
    (net (code "108") (name "/ROW0LED4") (class "Default")
      (node (ref "R53") (pin "1") (pinfunction "1_1") (pintype "passive"))
    )
    (net (code "109") (name "/ROW0LED5") (class "Default")
      (node (ref "R55") (pin "1") (pinfunction "1_1") (pintype "passive"))
    )
    (net (code "110") (name "/ROW0LED6") (class "Default")
      (node (ref "R57") (pin "1") (pinfunction "1_1") (pintype "passive"))
    )
    (net (code "111") (name "/ROW0LED7") (class "Default")
      (node (ref "R59") (pin "1") (pinfunction "1_1") (pintype "passive"))
    )
    (net (code "113") (name "/ROW1LED0") (class "Default")
      (node (ref "R30") (pin "1") (pinfunction "1_1") (pintype "passive"))
    )
    (net (code "114") (name "/ROW1LED1") (class "Default")
      (node (ref "R32") (pin "1") (pinfunction "1_1") (pintype "passive"))
    )
    (net (code "115") (name "/ROW1LED2") (class "Default")
      (node (ref "R34") (pin "1") (pinfunction "1_1") (pintype "passive"))
    )
    (net (code "116") (name "/ROW1LED3") (class "Default")
      (node (ref "R36") (pin "1") (pinfunction "1_1") (pintype "passive"))
    )
    (net (code "117") (name "/ROW1LED4") (class "Default")
      (node (ref "R37") (pin "1") (pinfunction "1_1") (pintype "passive"))
    )
    (net (code "118") (name "/ROW1LED5") (class "Default")
      (node (ref "R39") (pin "1") (pinfunction "1_1") (pintype "passive"))
    )
    (net (code "119") (name "/ROW1LED6") (class "Default")
      (node (ref "R41") (pin "1") (pinfunction "1_1") (pintype "passive"))
    )
    (net (code "120") (name "/ROW1LED7") (class "Default")
      (node (ref "R43") (pin "1") (pinfunction "1_1") (pintype "passive"))
    )
    (net (code "122") (name "/ROW2LED0") (class "Default")
      (node (ref "R62") (pin "2") (pinfunction "2_2") (pintype "passive"))
    )
    (net (code "123") (name "/ROW2LED1") (class "Default")
      (node (ref "R64") (pin "2") (pinfunction "2_2") (pintype "passive"))
    )
    (net (code "124") (name "/ROW2LED2") (class "Default")
      (node (ref "R66") (pin "2") (pinfunction "2_2") (pintype "passive"))
    )
    (net (code "125") (name "/ROW2LED3") (class "Default")
      (node (ref "R68") (pin "2") (pinfunction "2_2") (pintype "passive"))
    )
    (net (code "126") (name "/ROW2LED4") (class "Default")
      (node (ref "R69") (pin "2") (pinfunction "2_2") (pintype "passive"))
    )
    (net (code "127") (name "/ROW2LED5") (class "Default")
      (node (ref "R70") (pin "2") (pinfunction "2_2") (pintype "passive"))
    )
    (net (code "128") (name "/ROW2LED6") (class "Default")
      (node (ref "R71") (pin "2") (pinfunction "2_2") (pintype "passive"))
    )
    (net (code "129") (name "/ROW2LED7") (class "Default")
      (node (ref "R72") (pin "2") (pinfunction "2_2") (pintype "passive"))
    )
    (net (code "131") (name "/ROW3LED0") (class "Default")
      (node (ref "R25") (pin "2") (pinfunction "2_2") (pintype "passive"))
    )
    (net (code "132") (name "/ROW3LED1") (class "Default")
      (node (ref "R26") (pin "2") (pinfunction "2_2") (pintype "passive"))
    )
    (net (code "133") (name "/ROW3LED2") (class "Default")
      (node (ref "R27") (pin "2") (pinfunction "2_2") (pintype "passive"))
    )
    (net (code "134") (name "/ROW3LED3") (class "Default")
      (node (ref "R28") (pin "2") (pinfunction "2_2") (pintype "passive"))
    )
    (net (code "135") (name "/ROW3LED4") (class "Default")
      (node (ref "R29") (pin "2") (pinfunction "2_2") (pintype "passive"))
    )
    (net (code "136") (name "/ROW3LED5") (class "Default")
      (node (ref "R31") (pin "2") (pinfunction "2_2") (pintype "passive"))
    )
    (net (code "137") (name "/ROW3LED6") (class "Default")
      (node (ref "R33") (pin "2") (pinfunction "2_2") (pintype "passive"))
    )
    (net (code "138") (name "/ROW3LED7") (class "Default")
      (node (ref "R35") (pin "2") (pinfunction "2_2") (pintype "passive"))
    )
    (net (code "140") (name "/ROW4LED0") (class "Default")
      (node (ref "R38") (pin "2") (pinfunction "2_2") (pintype "passive"))
    )
    (net (code "141") (name "/ROW4LED1") (class "Default")
      (node (ref "R40") (pin "2") (pinfunction "2_2") (pintype "passive"))
    )
    (net (code "142") (name "/ROW4LED2") (class "Default")
      (node (ref "R42") (pin "2") (pinfunction "2_2") (pintype "passive"))
    )
    (net (code "143") (name "/ROW4LED3") (class "Default")
      (node (ref "R44") (pin "2") (pinfunction "2_2") (pintype "passive"))
    )
    (net (code "144") (name "/ROW4LED4") (class "Default")
      (node (ref "R45") (pin "2") (pinfunction "2_2") (pintype "passive"))
    )
    (net (code "145") (name "/ROW4LED5") (class "Default")
      (node (ref "R47") (pin "2") (pinfunction "2_2") (pintype "passive"))
    )
    (net (code "146") (name "/ROW4LED6") (class "Default")
      (node (ref "R49") (pin "2") (pinfunction "2_2") (pintype "passive"))
    )
    (net (code "147") (name "/ROW4LED7") (class "Default")
      (node (ref "R51") (pin "2") (pinfunction "2_2") (pintype "passive"))
    )
    (net (code "149") (name "/ROW5LED0") (class "Default")
      (node (ref "R54") (pin "2") (pinfunction "2_2") (pintype "passive"))
    )
    (net (code "150") (name "/ROW5LED1") (class "Default")
      (node (ref "R56") (pin "2") (pinfunction "2_2") (pintype "passive"))
    )
    (net (code "151") (name "/ROW5LED2") (class "Default")
      (node (ref "R58") (pin "2") (pinfunction "2_2") (pintype "passive"))
    )
    (net (code "152") (name "/ROW5LED3") (class "Default")
      (node (ref "R60") (pin "2") (pinfunction "2_2") (pintype "passive"))
    )
    (net (code "153") (name "/ROW5LED4") (class "Default")
      (node (ref "R61") (pin "2") (pinfunction "2_2") (pintype "passive"))
    )
    (net (code "154") (name "/ROW5LED5") (class "Default")
      (node (ref "R63") (pin "2") (pinfunction "2_2") (pintype "passive"))
    )
    (net (code "155") (name "/ROW5LED6") (class "Default")
      (node (ref "R65") (pin "2") (pinfunction "2_2") (pintype "passive"))
    )
    (net (code "156") (name "/ROW5LED7") (class "Default")
      (node (ref "R67") (pin "2") (pinfunction "2_2") (pintype "passive"))
    )
    (net (code "158") (name "/ROW6LED0") (class "Default")
      (node (ref "R4") (pin "1") (pinfunction "1_1") (pintype "passive"))
    )
    (net (code "159") (name "/ROW6LED1") (class "Default")
      (node (ref "R6") (pin "1") (pinfunction "1_1") (pintype "passive"))
    )
    (net (code "160") (name "/ROW6LED2") (class "Default")
      (node (ref "R8") (pin "1") (pinfunction "1_1") (pintype "passive"))
    )
    (net (code "161") (name "/ROW6LED3") (class "Default")
      (node (ref "R10") (pin "1") (pinfunction "1_1") (pintype "passive"))
    )
    (net (code "162") (name "/ROW6LED4") (class "Default")
      (node (ref "R12") (pin "1") (pinfunction "1_1") (pintype "passive"))
    )
    (net (code "163") (name "/ROW6LED5") (class "Default")
      (node (ref "R14") (pin "1") (pinfunction "1_1") (pintype "passive"))
    )
    (net (code "164") (name "/ROW6LED6") (class "Default")
      (node (ref "R15") (pin "1") (pinfunction "1_1") (pintype "passive"))
    )
    (net (code "165") (name "/ROW6LED7") (class "Default")
      (node (ref "R17") (pin "1") (pinfunction "1_1") (pintype "passive"))
    )
    (net (code "167") (name "/ROW7LED0") (class "Default")
      (node (ref "R1") (pin "1") (pinfunction "1_1") (pintype "passive"))
    )
    (net (code "168") (name "/ROW7LED1") (class "Default")
      (node (ref "R2") (pin "1") (pinfunction "1_1") (pintype "passive"))
    )
    (net (code "169") (name "/ROW7LED2") (class "Default")
      (node (ref "R3") (pin "1") (pinfunction "1_1") (pintype "passive"))
    )
    (net (code "170") (name "/ROW7LED3") (class "Default")
      (node (ref "R5") (pin "1") (pinfunction "1_1") (pintype "passive"))
    )
    (net (code "171") (name "/ROW7LED4") (class "Default")
      (node (ref "R7") (pin "1") (pinfunction "1_1") (pintype "passive"))
    )
    (net (code "172") (name "/ROW7LED5") (class "Default")
      (node (ref "R9") (pin "1") (pinfunction "1_1") (pintype "passive"))
    )
    (net (code "173") (name "/ROW7LED6") (class "Default")
      (node (ref "R11") (pin "1") (pinfunction "1_1") (pintype "passive"))
    )
    (net (code "174") (name "/ROW7LED7") (class "Default")
      (node (ref "R13") (pin "1") (pinfunction "1_1") (pintype "passive"))
    )
    (net (code "176") (name "/ROW8LED0") (class "Default")
      (node (ref "R16") (pin "1") (pinfunction "1_1") (pintype "passive"))
    )
    (net (code "177") (name "/ROW8LED1") (class "Default")
      (node (ref "R18") (pin "1") (pinfunction "1_1") (pintype "passive"))
    )
    (net (code "178") (name "/ROW8LED2") (class "Default")
      (node (ref "R19") (pin "1") (pinfunction "1_1") (pintype "passive"))
    )
    (net (code "179") (name "/ROW8LED3") (class "Default")
      (node (ref "R20") (pin "1") (pinfunction "1_1") (pintype "passive"))
    )
    (net (code "180") (name "/ROW8LED4") (class "Default")
      (node (ref "R21") (pin "1") (pinfunction "1_1") (pintype "passive"))
    )
    (net (code "181") (name "/ROW8LED5") (class "Default")
      (node (ref "R22") (pin "1") (pinfunction "1_1") (pintype "passive"))
    )
    (net (code "182") (name "/ROW8LED6") (class "Default")
      (node (ref "R23") (pin "1") (pinfunction "1_1") (pintype "passive"))
    )
    (net (code "183") (name "/ROW8LED7") (class "Default")
      (node (ref "R24") (pin "1") (pinfunction "1_1") (pintype "passive"))
    )
    (net (code "185") (name "/ROWON") (class "Default")
      (node (ref "J1") (pin "7") (pinfunction "7_7") (pintype "passive"))
    )
    (net (code "186") (name "/RSTGAME") (class "Default")
      (node (ref "J1") (pin "40") (pinfunction "40_40") (pintype "passive"))
    )
    (net (code "187") (name "/WRONG") (class "Default")
      (node (ref "J1") (pin "34") (pinfunction "34_34") (pintype "passive"))
    )
    (net (code "188") (name "GND") (class "Default")
      (node (ref "J1") (pin "28") (pinfunction "28_28") (pintype "passive"))
      (node (ref "J1") (pin "30") (pinfunction "30_30") (pintype "passive"))
      (node (ref "J2") (pin "30") (pinfunction "30_30") (pintype "passive"))
      (node (ref "J2") (pin "32") (pinfunction "32_32") (pintype "passive"))
      (node (ref "J2") (pin "34") (pinfunction "34_34") (pintype "passive"))
      (node (ref "J2") (pin "35") (pinfunction "35_35") (pintype "passive"))
      (node (ref "J2") (pin "36") (pinfunction "36_36") (pintype "passive"))
      (node (ref "J2") (pin "38") (pinfunction "38_38") (pintype "passive"))
      (node (ref "J2") (pin "39") (pinfunction "39_39") (pintype "passive"))
      (node (ref "J2") (pin "40") (pinfunction "40_40") (pintype "passive"))
      (node (ref "J3") (pin "10") (pinfunction "GND_10") (pintype "passive"))
      (node (ref "J3") (pin "21") (pinfunction "GND_21") (pintype "passive"))
      (node (ref "J3") (pin "22") (pinfunction "GND_22") (pintype "passive"))
      (node (ref "J3") (pin "32") (pinfunction "GND_32") (pintype "passive"))
      (node (ref "J3") (pin "33") (pinfunction "GND_33") (pintype "passive"))
      (node (ref "J3") (pin "44") (pinfunction "GND_44") (pintype "passive"))
      (node (ref "J3") (pin "53") (pinfunction "GND_53") (pintype "passive"))
      (node (ref "J3") (pin "54") (pinfunction "GND_54") (pintype "passive"))
      (node (ref "J3") (pin "76") (pinfunction "GND_76") (pintype "passive"))
    )
    (net (code "189") (name "VCC") (class "Default")
      (node (ref "J1") (pin "26") (pinfunction "26_26") (pintype "passive"))
      (node (ref "J3") (pin "79") (pinfunction "VCC5P0_79") (pintype "passive"))
      (node (ref "J3") (pin "80") (pinfunction "VCC5P0_80") (pintype "passive"))
    )
    (net (code "190") (name "unconnected-(J1-Pad15)") (class "Default")
      (node (ref "J1") (pin "15") (pinfunction "15_15") (pintype "passive+no_connect"))
    )
    (net (code "191") (name "unconnected-(J1-Pad20)") (class "Default")
      (node (ref "J1") (pin "20") (pinfunction "20_20") (pintype "passive+no_connect"))
    )
    (net (code "192") (name "unconnected-(J1-Pad22)") (class "Default")
      (node (ref "J1") (pin "22") (pinfunction "22_22") (pintype "passive+no_connect"))
    )
    (net (code "193") (name "unconnected-(J1-Pad24)") (class "Default")
      (node (ref "J1") (pin "24") (pinfunction "24_24") (pintype "passive+no_connect"))
    )
    (net (code "194") (name "unconnected-(J1-Pad29)") (class "Default")
      (node (ref "J1") (pin "29") (pinfunction "29_29") (pintype "passive+no_connect"))
    )
    (net (code "195") (name "unconnected-(J2-Pad2)") (class "Default")
      (node (ref "J2") (pin "2") (pinfunction "2_2") (pintype "passive+no_connect"))
    )
    (net (code "196") (name "unconnected-(J2-Pad6)") (class "Default")
      (node (ref "J2") (pin "6") (pinfunction "6_6") (pintype "passive+no_connect"))
    )
    (net (code "197") (name "unconnected-(J2-Pad10)") (class "Default")
      (node (ref "J2") (pin "10") (pinfunction "10_10") (pintype "passive+no_connect"))
    )
    (net (code "198") (name "unconnected-(J2-Pad14)") (class "Default")
      (node (ref "J2") (pin "14") (pinfunction "14_14") (pintype "passive+no_connect"))
    )
    (net (code "199") (name "unconnected-(J2-Pad18)") (class "Default")
      (node (ref "J2") (pin "18") (pinfunction "18_18") (pintype "passive+no_connect"))
    )
    (net (code "200") (name "unconnected-(J2-Pad22)") (class "Default")
      (node (ref "J2") (pin "22") (pinfunction "22_22") (pintype "passive+no_connect"))
    )
    (net (code "201") (name "unconnected-(J2-Pad24)") (class "Default")
      (node (ref "J2") (pin "24") (pinfunction "24_24") (pintype "passive+no_connect"))
    )
    (net (code "202") (name "unconnected-(J2-Pad37)") (class "Default")
      (node (ref "J2") (pin "37") (pinfunction "37_37") (pintype "passive+no_connect"))
    )
    (net (code "203") (name "unconnected-(J3-EG_P41-Pad20)") (class "Default")
      (node (ref "J3") (pin "20") (pinfunction "EG_P41_20") (pintype "passive+no_connect"))
    )
    (net (code "204") (name "unconnected-(J3-EG_P42-Pad24)") (class "Default")
      (node (ref "J3") (pin "24") (pinfunction "EG_P42_24") (pintype "passive+no_connect"))
    )
    (net (code "205") (name "unconnected-(J3-EG_P43-Pad26)") (class "Default")
      (node (ref "J3") (pin "26") (pinfunction "EG_P43_26") (pintype "passive+no_connect"))
    )
    (net (code "206") (name "unconnected-(J3-EG_P44-Pad28)") (class "Default")
      (node (ref "J3") (pin "28") (pinfunction "EG_P44_28") (pintype "passive+no_connect"))
    )
    (net (code "207") (name "unconnected-(J3-EG_P45-Pad30)") (class "Default")
      (node (ref "J3") (pin "30") (pinfunction "EG_P45_30") (pintype "passive+no_connect"))
    )
    (net (code "208") (name "unconnected-(J3-EG_P50-Pad42)") (class "Default")
      (node (ref "J3") (pin "42") (pinfunction "EG_P50_42") (pintype "passive+no_connect"))
    )
    (net (code "209") (name "unconnected-(J3-EG_P54-Pad52)") (class "Default")
      (node (ref "J3") (pin "52") (pinfunction "EG_P54_52") (pintype "passive+no_connect"))
    )
    (net (code "210") (name "unconnected-(J3-EXP_PRESENT-Pad78)") (class "Default")
      (node (ref "J3") (pin "78") (pinfunction "EXP_PRESENT_78") (pintype "passive+no_connect"))
    )
    (net (code "211") (name "unconnected-(J3-NC-Pad04)") (class "Default")
      (node (ref "J3") (pin "04") (pinfunction "NC_04") (pintype "passive+no_connect"))
    )
    (net (code "212") (name "unconnected-(J3-NC-Pad68)") (class "Default")
      (node (ref "J3") (pin "68") (pinfunction "NC_68") (pintype "passive+no_connect"))
    )
    (net (code "213") (name "unconnected-(J3-NC-Pad69)") (class "Default")
      (node (ref "J3") (pin "69") (pinfunction "NC_69") (pintype "passive+no_connect"))
    )
    (net (code "214") (name "unconnected-(J3-NC-Pad70)") (class "Default")
      (node (ref "J3") (pin "70") (pinfunction "NC_70") (pintype "passive+no_connect"))
    )
    (net (code "215") (name "unconnected-(J3-NC-Pad71)") (class "Default")
      (node (ref "J3") (pin "71") (pinfunction "NC_71") (pintype "passive+no_connect"))
    )
    (net (code "216") (name "unconnected-(J3-NC-Pad72)") (class "Default")
      (node (ref "J3") (pin "72") (pinfunction "NC_72") (pintype "passive+no_connect"))
    )
    (net (code "217") (name "unconnected-(J3-NC-Pad73)") (class "Default")
      (node (ref "J3") (pin "73") (pinfunction "NC_73") (pintype "passive+no_connect"))
    )
    (net (code "218") (name "unconnected-(J3-NC-Pad74)") (class "Default")
      (node (ref "J3") (pin "74") (pinfunction "NC_74") (pintype "passive+no_connect"))
    )
    (net (code "219") (name "unconnected-(J3-NC-Pad75)") (class "Default")
      (node (ref "J3") (pin "75") (pinfunction "NC_75") (pintype "passive+no_connect"))
    )
    (net (code "220") (name "unconnected-(J3-NC-Pad77)") (class "Default")
      (node (ref "J3") (pin "77") (pinfunction "NC_77") (pintype "passive+no_connect"))
    )
    (net (code "221") (name "unconnected-(J3-RESET_EXP#-Pad03)") (class "Default")
      (node (ref "J3") (pin "03") (pinfunction "RESET_EXP#_03") (pintype "passive+no_connect"))
    )
    (net (code "222") (name "unconnected-(J3-VCC3P3-Pad01)") (class "Default")
      (node (ref "J3") (pin "01") (pinfunction "VCC3P3_01") (pintype "passive+no_connect"))
    )
    (net (code "223") (name "unconnected-(J3-VCC3P3-Pad02)") (class "Default")
      (node (ref "J3") (pin "02") (pinfunction "VCC3P3_02") (pintype "passive+no_connect"))
    )
  )
)
